# Schematic_SchDoc.net
KiCad netlist of a schematic drawn in Altium Designer
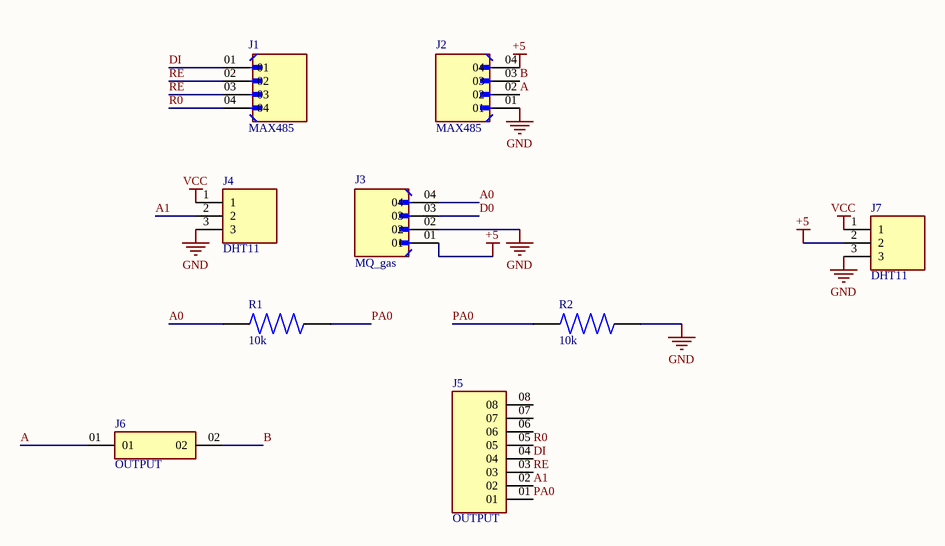
[diagram p0: Schematic.SchDoc.SchDoc]

(export (version "E")
  (design (tool "Eeschema 10.0.6"))
  (components
    (comp (ref "J1")
      (value "MAX485")
      (footprint "WURTH_61300411121")
      (description "Connector Header Through Hole 4 position 0.100 (2.54mm)")
      (fields (field (name "MF") "WÃ¼rth Elektronik") (field (name "MP") "61300411121"))
      (libsource (lib "") (part "61300411121_1"))
    )
    (comp (ref "J2")
      (value "MAX485")
      (footprint "WURTH_61300411121")
      (description "Connector Header Through Hole 4 position 0.100 (2.54mm)")
      (fields (field (name "MF") "WÃ¼rth Elektronik") (field (name "MP") "61300411121"))
      (libsource (lib "61300411121") (part "61300411121"))
    )
    (comp (ref "J3")
      (value "MQ_gas")
      (footprint "WURTH_61300411121")
      (description "Connector Header Through Hole 4 position 0.100 (2.54mm)")
      (fields (field (name "MF") "WÃ¼rth Elektronik") (field (name "MP") "61300411121"))
      (libsource (lib "61300411121") (part "61300411121"))
    )
    (comp (ref "J4")
      (value "DHT11")
      (footprint "TE_644884-3")
      (description "Conn Unshrouded Header HDR 3 POS 2.54mm Solder ST Thru-Hole Bag/Box")
      (fields (field (name "MF") "TE Connectivity") (field (name "MP") "644884-3"))
      (libsource (lib "644884-3") (part "644884-3"))
    )
    (comp (ref "J5")
      (value "OUTPUT")
      (footprint "SAMTEC_TSW-108-X-X-S")
      (description "Connector Header Through Hole 8 position 0.100 (2.54mm)")
      (fields (field (name "MF") "Samtec") (field (name "MP") "TSW-108-23-L-S"))
      (libsource (lib "TSW-108-X-X-S") (part "TSW-108-X-X-S"))
    )
    (comp (ref "J6")
      (value "OUTPUT")
      (footprint "SAMTEC_MTSW-101-08-S-D-318")
      (fields (field (name "MP") "MTSW-101-08-S-D-318"))
      (libsource (lib "MTSW-101-08-S-D-318") (part "MTSW-101-08-S-D-318"))
    )
    (comp (ref "J7")
      (value "DHT11")
      (footprint "TE_644884-3")
      (description "Conn Unshrouded Header HDR 3 POS 2.54mm Solder ST Thru-Hole Bag/Box")
      (fields (field (name "MF") "TE Connectivity") (field (name "MP") "644884-3"))
      (libsource (lib "644884-3") (part "644884-3"))
    )
    (comp (ref "R1")
      (value "10k")
      (footprint "RESAD1100W55L680D260")
      (description "1.07 kOhms Â±1% 0.25W, 1/4W Through Hole Resistor Axial - Metal Film")
      (fields (field (name "MF") "Yageo") (field (name "MP") "MFR-25FBF52-1K"))
      (libsource (lib "MFR-25FBF52-1K") (part "MFR-25FBF52-1K"))
    )
    (comp (ref "R2")
      (value "10k")
      (footprint "RESAD1100W55L680D260")
      (description "1.07 kOhms Â±1% 0.25W, 1/4W Through Hole Resistor Axial - Metal Film")
      (fields (field (name "MF") "Yageo") (field (name "MP") "MFR-25FBF52-1K"))
      (libsource (lib "MFR-25FBF52-1K") (part "MFR-25FBF52-1K"))
    )
  )
  (nets
    (net (code "1") (name "+5") (class "Default")
      (node (ref "J2") (pin "04") (pinfunction "04_04") (pintype "passive"))
      (node (ref "J3") (pin "01") (pinfunction "01_01") (pintype "passive"))
      (node (ref "J7") (pin "2") (pinfunction "2_2") (pintype "passive"))
    )
    (net (code "2") (name "/A") (class "Default")
      (node (ref "J2") (pin "02") (pinfunction "02_02") (pintype "passive"))
      (node (ref "J6") (pin "01") (pinfunction "01_01") (pintype "passive"))
    )
    (net (code "3") (name "/A0") (class "Default")
      (node (ref "J3") (pin "04") (pinfunction "04_04") (pintype "passive"))
      (node (ref "R1") (pin "1") (pinfunction "1_1") (pintype "passive"))
    )
    (net (code "4") (name "/A1") (class "Default")
      (node (ref "J4") (pin "2") (pinfunction "2_2") (pintype "passive"))
      (node (ref "J5") (pin "02") (pinfunction "02_02") (pintype "passive"))
    )
    (net (code "5") (name "/B") (class "Default")
      (node (ref "J2") (pin "03") (pinfunction "03_03") (pintype "passive"))
      (node (ref "J6") (pin "02") (pinfunction "02_02") (pintype "passive"))
    )
    (net (code "6") (name "/D0") (class "Default")
      (node (ref "J3") (pin "03") (pinfunction "03_03") (pintype "passive"))
    )
    (net (code "7") (name "/DI") (class "Default")
      (node (ref "J1") (pin "01") (pinfunction "01_01") (pintype "passive"))
      (node (ref "J5") (pin "04") (pinfunction "04_04") (pintype "passive"))
    )
    (net (code "8") (name "/PA0") (class "Default")
      (node (ref "J5") (pin "01") (pinfunction "01_01") (pintype "passive"))
      (node (ref "R1") (pin "2") (pinfunction "2_2") (pintype "passive"))
      (node (ref "R2") (pin "1") (pinfunction "1_1") (pintype "passive"))
    )
    (net (code "9") (name "/R0") (class "Default")
      (node (ref "J1") (pin "04") (pinfunction "04_04") (pintype "passive"))
      (node (ref "J5") (pin "05") (pinfunction "05_05") (pintype "passive"))
    )
    (net (code "10") (name "/RE") (class "Default")
      (node (ref "J1") (pin "02") (pinfunction "02_02") (pintype "passive"))
      (node (ref "J1") (pin "03") (pinfunction "03_03") (pintype "passive"))
      (node (ref "J5") (pin "03") (pinfunction "03_03") (pintype "passive"))
    )
    (net (code "11") (name "GND") (class "Default")
      (node (ref "J2") (pin "01") (pinfunction "01_01") (pintype "passive"))
      (node (ref "J3") (pin "02") (pinfunction "02_02") (pintype "passive"))
      (node (ref "J4") (pin "3") (pinfunction "3_3") (pintype "passive"))
      (node (ref "J7") (pin "3") (pinfunction "3_3") (pintype "passive"))
      (node (ref "R2") (pin "2") (pinfunction "2_2") (pintype "passive"))
    )
    (net (code "12") (name "VCC") (class "Default")
      (node (ref "J4") (pin "1") (pinfunction "1_1") (pintype "passive"))
      (node (ref "J7") (pin "1") (pinfunction "1_1") (pintype "passive"))
    )
    (net (code "13") (name "unconnected-(J5-Pad06)") (class "Default")
      (node (ref "J5") (pin "06") (pinfunction "06_06") (pintype "passive"))
    )
    (net (code "14") (name "unconnected-(J5-Pad07)") (class "Default")
      (node (ref "J5") (pin "07") (pinfunction "07_07") (pintype "passive"))
    )
    (net (code "15") (name "unconnected-(J5-Pad08)") (class "Default")
      (node (ref "J5") (pin "08") (pinfunction "08_08") (pintype "passive"))
    )
  )
)
